# CC_CHANNEL.net
KiCad netlist of a schematic drawn in Altium Designer
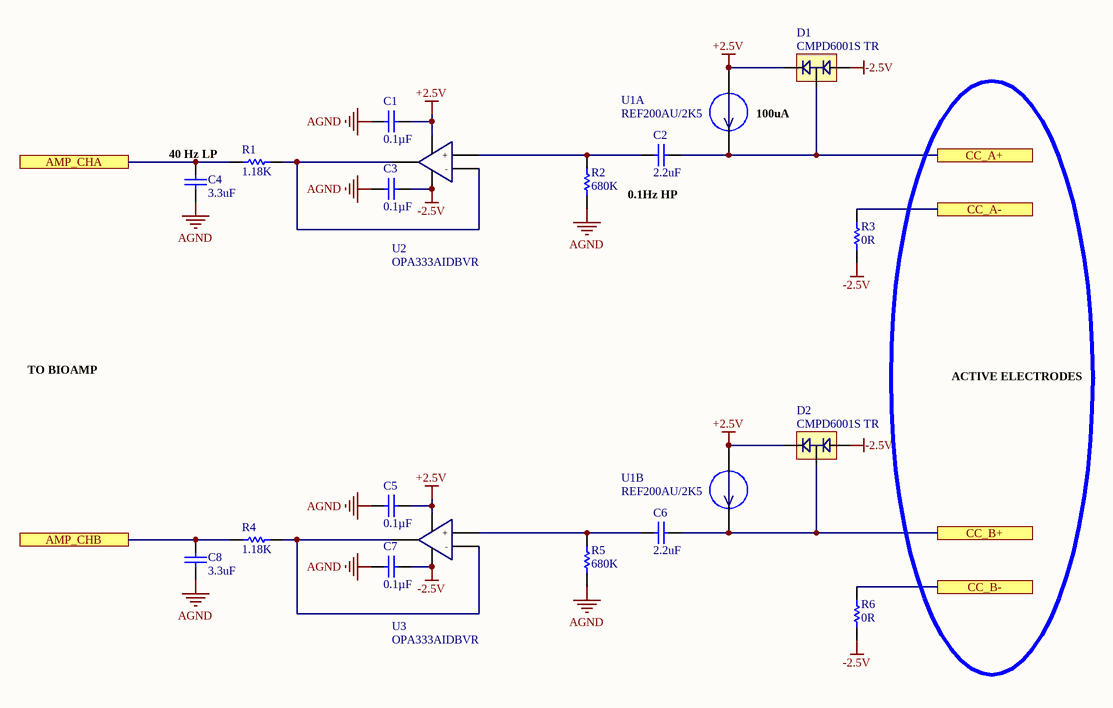
[diagram p0: CC CHANNEL.SchDoc]

(export (version "E")
  (design (tool "Eeschema 10.0.6"))
  (components
    (comp (ref "C1")
      (value "~")
      (footprint "0805C")
      (description "CAP .1UF 50V CERAMIC Y5V 0805")
      (fields
        (field (name "MANUFACTURER") "AVX Corporation")
        (field (name "MANUFACTURER PART NUMBER") "08055C104KAT2A")
        (field (name "CAPACITANCE") "0.1µF")
      )
      (libsource (lib "Miscellaneous Devices") (part "Cap"))
    )
    (comp (ref "C2")
      (value "50V")
      (footprint "0805C")
      (description "CAP .1UF 50V CERAMIC Y5V 0805")
      (fields
        (field (name "CAPACITANCE") "2.2uF")
        (field (name "MANUFACTURER") "Yageo")
        (field (name "MANUFACTURER PART NUMBER") "CC0805MRX5R6BB225")
      )
      (libsource (lib "Miscellaneous Devices") (part "Cap"))
    )
    (comp (ref "C3")
      (value "~")
      (footprint "0805C")
      (description "CAP .1UF 50V CERAMIC Y5V 0805")
      (fields
        (field (name "MANUFACTURER") "AVX Corporation")
        (field (name "MANUFACTURER PART NUMBER") "08055C104KAT2A")
        (field (name "CAPACITANCE") "0.1µF")
      )
      (libsource (lib "Miscellaneous Devices") (part "Cap"))
    )
    (comp (ref "C4")
      (value "~")
      (footprint "0805C")
      (description "CAP .1UF 50V CERAMIC Y5V 0805")
      (fields
        (field (name "CAPACITANCE") "3.3uF")
        (field (name "MANUFACTURER") "TDK Corporation")
        (field (name "MANUFACTURER PART NUMBER") "CGA4J3X7R1C335K125AB")
      )
      (libsource (lib "Miscellaneous Devices") (part "Cap"))
    )
    (comp (ref "C5")
      (value "~")
      (footprint "0805C")
      (description "CAP .1UF 50V CERAMIC Y5V 0805")
      (fields
        (field (name "MANUFACTURER") "AVX Corporation")
        (field (name "MANUFACTURER PART NUMBER") "08055C104KAT2A")
        (field (name "CAPACITANCE") "0.1µF")
      )
      (libsource (lib "Miscellaneous Devices") (part "Cap"))
    )
    (comp (ref "C6")
      (value "50V")
      (footprint "0805C")
      (description "CAP .1UF 50V CERAMIC Y5V 0805")
      (fields
        (field (name "CAPACITANCE") "2.2uF")
        (field (name "MANUFACTURER") "Yageo")
        (field (name "MANUFACTURER PART NUMBER") "CC0805MRX5R6BB225")
      )
      (libsource (lib "Miscellaneous Devices") (part "Cap"))
    )
    (comp (ref "C7")
      (value "~")
      (footprint "0805C")
      (description "CAP .1UF 50V CERAMIC Y5V 0805")
      (fields
        (field (name "MANUFACTURER") "AVX Corporation")
        (field (name "MANUFACTURER PART NUMBER") "08055C104KAT2A")
        (field (name "CAPACITANCE") "0.1µF")
      )
      (libsource (lib "Miscellaneous Devices") (part "Cap"))
    )
    (comp (ref "C8")
      (value "~")
      (footprint "0805C")
      (description "CAP .1UF 50V CERAMIC Y5V 0805")
      (fields
        (field (name "CAPACITANCE") "3.3uF")
        (field (name "MANUFACTURER") "TDK Corporation")
        (field (name "MANUFACTURER PART NUMBER") "CGA4J3X7R1C335K125AB")
      )
      (libsource (lib "Miscellaneous Devices") (part "Cap"))
    )
    (comp (ref "D1")
      (value "CMPD6001S TR")
      (footprint "SOT-23")
      (fields
        (field (name "MANUFACTURER") "Central Semiconductor Corp")
        (field (name "MANUFACTURER PART NUMBER") "CMPD6001S TR")
      )
      (libsource (lib "EEG_SCHLIB") (part "CMPD6001S TR"))
    )
    (comp (ref "D2")
      (value "CMPD6001S TR")
      (footprint "SOT-23")
      (fields
        (field (name "MANUFACTURER") "Central Semiconductor Corp")
        (field (name "MANUFACTURER PART NUMBER") "CMPD6001S TR")
      )
      (libsource (lib "EEG_SCHLIB") (part "CMPD6001S TR"))
    )
    (comp (ref "R1")
      (value "Res 0805")
      (footprint "0805R")
      (description "Resistor")
      (fields
        (field (name "RESISTANCE (OHMS)") "1.18K")
        (field (name "MANUFACTURER") "Yageo")
        (field (name "MANUFACTURER PART NUMBER") "RC0805FR-071K18L")
      )
      (libsource (lib "RAPTOR MCB SCHLIB") (part "Res 0805"))
    )
    (comp (ref "R2")
      (value "Res 0805")
      (footprint "0805R")
      (description "Resistor")
      (fields
        (field (name "RESISTANCE (OHMS)") "680K")
        (field (name "MANUFACTURER") "Panasonic Electronic Components")
        (field (name "MANUFACTURER PART NUMBER") "ERJ-6ENF6803V")
      )
      (libsource (lib "RAPTOR MCB SCHLIB") (part "Res 0805"))
    )
    (comp (ref "R3")
      (value "Res 0805")
      (footprint "0805R")
      (description "Resistor")
      (fields
        (field (name "MANUFACTURER") "Panasonic Electronic Components")
        (field (name "MANUFACTURER PART NUMBER") "ERJ-6GEY0R00V")
        (field (name "RESISTANCE (OHMS)") "0R")
      )
      (libsource (lib "RAPTOR MCB SCHLIB") (part "Res 0805"))
    )
    (comp (ref "R4")
      (value "Res 0805")
      (footprint "0805R")
      (description "Resistor")
      (fields
        (field (name "RESISTANCE (OHMS)") "1.18K")
        (field (name "MANUFACTURER") "Yageo")
        (field (name "MANUFACTURER PART NUMBER") "RC0805FR-071K18L")
      )
      (libsource (lib "RAPTOR MCB SCHLIB") (part "Res 0805"))
    )
    (comp (ref "R5")
      (value "Res 0805")
      (footprint "0805R")
      (description "Resistor")
      (fields
        (field (name "RESISTANCE (OHMS)") "680K")
        (field (name "MANUFACTURER") "Panasonic Electronic Components")
        (field (name "MANUFACTURER PART NUMBER") "ERJ-6ENF6803V")
      )
      (libsource (lib "RAPTOR MCB SCHLIB") (part "Res 0805"))
    )
    (comp (ref "R6")
      (value "Res 0805")
      (footprint "0805R")
      (description "Resistor")
      (fields
        (field (name "MANUFACTURER") "Panasonic Electronic Components")
        (field (name "MANUFACTURER PART NUMBER") "ERJ-6GEY0R00V")
        (field (name "RESISTANCE (OHMS)") "0R")
      )
      (libsource (lib "RAPTOR MCB SCHLIB") (part "Res 0805"))
    )
    (comp (ref "U1")
      (value "REF200AU/2K5")
      (footprint "SOIC-8")
      (fields
        (field (name "MANUFACTURER") "Texas Instruments")
        (field (name "BASE PART NUMBER") "REF200")
        (field (name "MANUFACTURER PART NUMBER") "REF200AU/2K5")
      )
      (libsource (lib "CC BREAKOUT BOARD SCHLIB") (part "REF200AU/2K5"))
    )
    (comp (ref "U2")
      (value "LPV821DBVR")
      (footprint "SOT-23-5")
      (fields
        (field (name "MANUFACTURER") "Texas Instruments")
        (field (name "MANUFACTURER PART NUMBER") "OPA333AIDBVR")
      )
      (libsource (lib "CC BREAKOUT BOARD SCHLIB") (part "LPV821DBVR"))
    )
    (comp (ref "U3")
      (value "LPV821DBVR")
      (footprint "SOT-23-5")
      (fields
        (field (name "MANUFACTURER") "Texas Instruments")
        (field (name "MANUFACTURER PART NUMBER") "OPA333AIDBVR")
      )
      (libsource (lib "CC BREAKOUT BOARD SCHLIB") (part "LPV821DBVR"))
    )
  )
  (nets
    (net (code "1") (name "+2.5V") (class "Default")
      (node (ref "C1") (pin "2") (pinfunction "2_2") (pintype "passive"))
      (node (ref "C5") (pin "2") (pinfunction "2_2") (pintype "passive"))
      (node (ref "D1") (pin "2") (pinfunction "2_2") (pintype "passive"))
      (node (ref "D2") (pin "2") (pinfunction "2_2") (pintype "passive"))
      (node (ref "U1") (pin "7") (pinfunction "I2_HIGH_7") (pintype "passive"))
      (node (ref "U1") (pin "8") (pinfunction "I1_HIGH_8") (pintype "passive"))
      (node (ref "U2") (pin "5") (pinfunction "VCC_5") (pintype "passive"))
      (node (ref "U3") (pin "5") (pinfunction "VCC_5") (pintype "passive"))
    )
    (net (code "2") (name "-2.5V") (class "Default")
      (node (ref "C3") (pin "2") (pinfunction "2_2") (pintype "passive"))
      (node (ref "C7") (pin "2") (pinfunction "2_2") (pintype "passive"))
      (node (ref "D1") (pin "1") (pinfunction "1_1") (pintype "passive"))
      (node (ref "D2") (pin "1") (pinfunction "1_1") (pintype "passive"))
      (node (ref "R3") (pin "1") (pinfunction "1_1") (pintype "passive"))
      (node (ref "R6") (pin "1") (pinfunction "1_1") (pintype "passive"))
      (node (ref "U2") (pin "2") (pinfunction "VDD_2") (pintype "passive"))
      (node (ref "U3") (pin "2") (pinfunction "VDD_2") (pintype "passive"))
    )
    (net (code "3") (name "/AMP_CHA") (class "Default")
      (node (ref "C4") (pin "2") (pinfunction "2_2") (pintype "passive"))
      (node (ref "R1") (pin "2") (pinfunction "2_2") (pintype "passive"))
    )
    (net (code "4") (name "/AMP_CHB") (class "Default")
      (node (ref "C8") (pin "2") (pinfunction "2_2") (pintype "passive"))
      (node (ref "R4") (pin "2") (pinfunction "2_2") (pintype "passive"))
    )
    (net (code "5") (name "/CC_A+") (class "Default")
      (node (ref "C2") (pin "1") (pinfunction "1_1") (pintype "passive"))
      (node (ref "D1") (pin "3") (pinfunction "3_3") (pintype "passive"))
      (node (ref "U1") (pin "1") (pinfunction "I1_LOW_1") (pintype "passive"))
    )
    (net (code "6") (name "/CC_A-") (class "Default")
      (node (ref "R3") (pin "2") (pinfunction "2_2") (pintype "passive"))
    )
    (net (code "7") (name "/CC_B+") (class "Default")
      (node (ref "C6") (pin "1") (pinfunction "1_1") (pintype "passive"))
      (node (ref "D2") (pin "3") (pinfunction "3_3") (pintype "passive"))
      (node (ref "U1") (pin "2") (pinfunction "I2_LOW_2") (pintype "passive"))
    )
    (net (code "8") (name "/CC_B-") (class "Default")
      (node (ref "R6") (pin "2") (pinfunction "2_2") (pintype "passive"))
    )
    (net (code "9") (name "AGND") (class "Default")
      (node (ref "C1") (pin "1") (pinfunction "1_1") (pintype "passive"))
      (node (ref "C3") (pin "1") (pinfunction "1_1") (pintype "passive"))
      (node (ref "C4") (pin "1") (pinfunction "1_1") (pintype "passive"))
      (node (ref "C5") (pin "1") (pinfunction "1_1") (pintype "passive"))
      (node (ref "C7") (pin "1") (pinfunction "1_1") (pintype "passive"))
      (node (ref "C8") (pin "1") (pinfunction "1_1") (pintype "passive"))
      (node (ref "R2") (pin "1") (pinfunction "1_1") (pintype "passive"))
      (node (ref "R5") (pin "1") (pinfunction "1_1") (pintype "passive"))
    )
    (net (code "10") (name "Net-(U2-+)") (class "Default")
      (node (ref "C2") (pin "2") (pinfunction "2_2") (pintype "passive"))
      (node (ref "R2") (pin "2") (pinfunction "2_2") (pintype "passive"))
      (node (ref "U2") (pin "3") (pinfunction "+_3") (pintype "passive"))
    )
    (net (code "11") (name "Net-(U2--)") (class "Default")
      (node (ref "R1") (pin "1") (pinfunction "1_1") (pintype "passive"))
      (node (ref "U2") (pin "1") (pinfunction "OUT_1") (pintype "passive"))
      (node (ref "U2") (pin "4") (pinfunction "-_4") (pintype "passive"))
    )
    (net (code "12") (name "Net-(U3-+)") (class "Default")
      (node (ref "C6") (pin "2") (pinfunction "2_2") (pintype "passive"))
      (node (ref "R5") (pin "2") (pinfunction "2_2") (pintype "passive"))
      (node (ref "U3") (pin "3") (pinfunction "+_3") (pintype "passive"))
    )
    (net (code "13") (name "Net-(U3--)") (class "Default")
      (node (ref "R4") (pin "1") (pinfunction "1_1") (pintype "passive"))
      (node (ref "U3") (pin "1") (pinfunction "OUT_1") (pintype "passive"))
      (node (ref "U3") (pin "4") (pinfunction "-_4") (pintype "passive"))
    )
  )
)
